# MAGI_sUART.net
KiCad netlist of a schematic drawn in Altium Designer
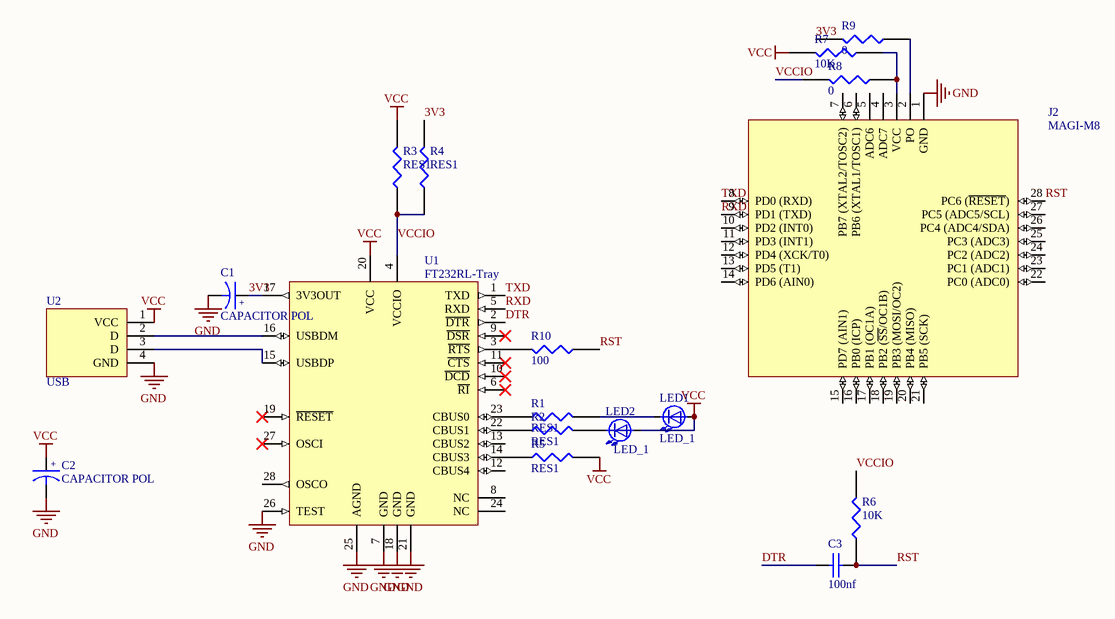
[diagram p0: MAGI'sUART.SchDoc]

(export (version "E")
  (design (tool "Eeschema 10.0.6"))
  (components
    (comp (ref "C1")
      (value "CAPACITOR POL")
      (footprint "6-0805_N")
      (description "Capacitor")
      (libsource (lib "电容器") (part "CAPACITOR POL"))
    )
    (comp (ref "C2")
      (value "CAPACITOR POL")
      (footprint "6-0805_N")
      (description "Capacitor")
      (libsource (lib "电容器") (part "CAPACITOR POL"))
    )
    (comp (ref "C3")
      (value "100nf")
      (footprint "6-0805_n")
      (description "Capacitor")
      (libsource (lib "电容器") (part "CAP_1"))
    )
    (comp (ref "J2") (value "MAGI-M8") (footprint "MAGI-M8") (libsource (lib "MAGI-M8") (part "MAGI-M8")))
    (comp (ref "LED1") (value "LED_1") (footprint "6-0805_N") (libsource (lib "二极管") (part "LED_1")))
    (comp (ref "LED2") (value "LED_1") (footprint "6-0805_N") (libsource (lib "二极管") (part "LED_1")))
    (comp (ref "R1") (value "RES1") (footprint "6-0805_n") (libsource (lib "电阻器") (part "RES1")))
    (comp (ref "R2") (value "RES1") (footprint "6-0805_n") (libsource (lib "电阻器") (part "RES1")))
    (comp (ref "R3") (value "RES1") (footprint "6-0805_N") (libsource (lib "电阻器") (part "RES1")))
    (comp (ref "R4") (value "RES1") (footprint "6-0805_N") (libsource (lib "电阻器") (part "RES1")))
    (comp (ref "R5") (value "RES1") (footprint "6-0805_N") (libsource (lib "电阻器") (part "RES1")))
    (comp (ref "R6") (value "10K") (footprint "6-0805_N") (libsource (lib "电阻器") (part "RES1")))
    (comp (ref "R7") (value "10K") (footprint "6-0805_N") (libsource (lib "电阻器") (part "RES1")))
    (comp (ref "R8") (value "0") (footprint "6-0805_N") (libsource (lib "电阻器") (part "RES1")))
    (comp (ref "R9") (value "0") (footprint "6-0805_N") (libsource (lib "电阻器") (part "RES1")))
    (comp (ref "R10") (value "100") (footprint "6-0805_N") (libsource (lib "电阻器") (part "RES1")))
    (comp (ref "U1")
      (value "FT232RL-Tray")
      (footprint "SSOP-28_N")
      (description "USB UART Asynchronous Serial Data Transfer Chip, SSOP-28, Tray")
      (fields (field (name "PUBLISHER") "Altium Limited"))
      (libsource (lib "FTDI Communication UART") (part "FT232RL-Tray"))
    )
    (comp (ref "U2") (value "USB") (footprint "MicroUSB") (libsource (lib "USB接口") (part "USB")))
  )
  (nets
    (net (code "1") (name "/3V3") (class "Default")
      (node (ref "C1") (pin "1") (pinfunction "1_1") (pintype "passive"))
      (node (ref "R4") (pin "2") (pinfunction "2_2") (pintype "passive"))
      (node (ref "R9") (pin "2") (pinfunction "2_2") (pintype "passive"))
      (node (ref "U1") (pin "17") (pinfunction "3V3OUT_17") (pintype "output"))
    )
    (net (code "2") (name "/DTR") (class "Default")
      (node (ref "C3") (pin "1") (pinfunction "1_1") (pintype "passive"))
      (node (ref "U1") (pin "2") (pinfunction "~{DTR}_2") (pintype "output"))
    )
    (net (code "3") (name "/RST") (class "Default")
      (node (ref "C3") (pin "2") (pinfunction "2_2") (pintype "passive"))
      (node (ref "J2") (pin "28") (pinfunction "PC6_(~{RESET})_28") (pintype "bidirectional"))
      (node (ref "R10") (pin "1") (pinfunction "1_1") (pintype "passive"))
      (node (ref "R6") (pin "1") (pinfunction "1_1") (pintype "passive"))
    )
    (net (code "4") (name "/RXD") (class "Default")
      (node (ref "J2") (pin "9") (pinfunction "PD1_(TXD)_9") (pintype "bidirectional"))
      (node (ref "U1") (pin "5") (pinfunction "RXD_5") (pintype "input"))
    )
    (net (code "5") (name "/TXD") (class "Default")
      (node (ref "J2") (pin "8") (pinfunction "PD0_(RXD)_8") (pintype "bidirectional"))
      (node (ref "U1") (pin "1") (pinfunction "TXD_1") (pintype "output"))
    )
    (net (code "6") (name "/VCCIO") (class "Default")
      (node (ref "R3") (pin "1") (pinfunction "1_1") (pintype "passive"))
      (node (ref "R4") (pin "1") (pinfunction "1_1") (pintype "passive"))
      (node (ref "R6") (pin "2") (pinfunction "2_2") (pintype "passive"))
      (node (ref "R8") (pin "2") (pinfunction "2_2") (pintype "passive"))
      (node (ref "U1") (pin "4") (pinfunction "VCCIO_4") (pintype "power_in"))
    )
    (net (code "7") (name "GND") (class "Default")
      (node (ref "C1") (pin "2") (pinfunction "2_2") (pintype "passive"))
      (node (ref "C2") (pin "2") (pinfunction "2_2") (pintype "passive"))
      (node (ref "J2") (pin "1") (pinfunction "GND_1") (pintype "power_in"))
      (node (ref "U1") (pin "18") (pinfunction "GND_18") (pintype "power_in"))
      (node (ref "U1") (pin "21") (pinfunction "GND_21") (pintype "power_in"))
      (node (ref "U1") (pin "25") (pinfunction "AGND_25") (pintype "power_in"))
      (node (ref "U1") (pin "26") (pinfunction "TEST_26") (pintype "input"))
      (node (ref "U1") (pin "7") (pinfunction "GND_7") (pintype "power_in"))
      (node (ref "U2") (pin "4") (pinfunction "GND_4") (pintype "passive"))
    )
    (net (code "8") (name "Net-(J2-PO)") (class "Default")
      (node (ref "J2") (pin "2") (pinfunction "PO_2") (pintype "power_in"))
      (node (ref "R9") (pin "1") (pinfunction "1_1") (pintype "passive"))
    )
    (net (code "9") (name "Net-(J2-VCC)") (class "Default")
      (node (ref "J2") (pin "3") (pinfunction "VCC_3") (pintype "power_in"))
      (node (ref "R7") (pin "1") (pinfunction "1_1") (pintype "passive"))
      (node (ref "R8") (pin "1") (pinfunction "1_1") (pintype "passive"))
    )
    (net (code "10") (name "Net-(LED1-K)") (class "Default")
      (node (ref "LED1") (pin "2") (pinfunction "K_2") (pintype "passive"))
      (node (ref "R1") (pin "2") (pinfunction "2_2") (pintype "passive"))
    )
    (net (code "11") (name "Net-(LED2-K)") (class "Default")
      (node (ref "LED2") (pin "2") (pinfunction "K_2") (pintype "passive"))
      (node (ref "R2") (pin "2") (pinfunction "2_2") (pintype "passive"))
    )
    (net (code "12") (name "Net-(U1-CBUS0)") (class "Default")
      (node (ref "R1") (pin "1") (pinfunction "1_1") (pintype "passive"))
      (node (ref "U1") (pin "23") (pinfunction "CBUS0_23") (pintype "bidirectional"))
    )
    (net (code "13") (name "Net-(U1-CBUS1)") (class "Default")
      (node (ref "R2") (pin "1") (pinfunction "1_1") (pintype "passive"))
      (node (ref "U1") (pin "22") (pinfunction "CBUS1_22") (pintype "bidirectional"))
    )
    (net (code "14") (name "Net-(U1-CBUS3)") (class "Default")
      (node (ref "R5") (pin "1") (pinfunction "1_1") (pintype "passive"))
      (node (ref "U1") (pin "14") (pinfunction "CBUS3_14") (pintype "bidirectional"))
    )
    (net (code "15") (name "Net-(U1-USBDM)") (class "Default")
      (node (ref "U1") (pin "16") (pinfunction "USBDM_16") (pintype "bidirectional"))
      (node (ref "U2") (pin "2") (pinfunction "D_2") (pintype "passive"))
    )
    (net (code "16") (name "Net-(U1-USBDP)") (class "Default")
      (node (ref "U1") (pin "15") (pinfunction "USBDP_15") (pintype "bidirectional"))
      (node (ref "U2") (pin "3") (pinfunction "D_3") (pintype "passive"))
    )
    (net (code "17") (name "Net-(U1-~{RTS})") (class "Default")
      (node (ref "R10") (pin "2") (pinfunction "2_2") (pintype "passive"))
      (node (ref "U1") (pin "3") (pinfunction "~{RTS}_3") (pintype "output"))
    )
    (net (code "18") (name "VCC") (class "Default")
      (node (ref "C2") (pin "1") (pinfunction "1_1") (pintype "passive"))
      (node (ref "LED1") (pin "1") (pinfunction "A_1") (pintype "passive"))
      (node (ref "LED2") (pin "1") (pinfunction "A_1") (pintype "passive"))
      (node (ref "R3") (pin "2") (pinfunction "2_2") (pintype "passive"))
      (node (ref "R5") (pin "2") (pinfunction "2_2") (pintype "passive"))
      (node (ref "R7") (pin "2") (pinfunction "2_2") (pintype "passive"))
      (node (ref "U1") (pin "20") (pinfunction "VCC_20") (pintype "power_in"))
      (node (ref "U2") (pin "1") (pinfunction "VCC_1") (pintype "passive"))
    )
    (net (code "19") (name "unconnected-(J2-ADC6-Pad5)") (class "Default")
      (node (ref "J2") (pin "5") (pinfunction "ADC6_5") (pintype "passive"))
    )
    (net (code "20") (name "unconnected-(J2-ADC7-Pad4)") (class "Default")
      (node (ref "J2") (pin "4") (pinfunction "ADC7_4") (pintype "passive"))
    )
    (net (code "21") (name "unconnected-(J2-PB0_(ICP)-Pad16)") (class "Default")
      (node (ref "J2") (pin "16") (pinfunction "PB0_(ICP)_16") (pintype "bidirectional"))
    )
    (net (code "22") (name "unconnected-(J2-PB1_(OC1A)-Pad17)") (class "Default")
      (node (ref "J2") (pin "17") (pinfunction "PB1_(OC1A)_17") (pintype "bidirectional"))
    )
    (net (code "23") (name "unconnected-(J2-PB2_(~{SS}{slash}OC1B)-Pad18)") (class "Default")
      (node (ref "J2") (pin "18") (pinfunction "PB2_(~{SS}/OC1B)_18") (pintype "bidirectional"))
    )
    (net (code "24") (name "unconnected-(J2-PB3_(MOSI{slash}OC2)-Pad19)") (class "Default")
      (node (ref "J2") (pin "19") (pinfunction "PB3_(MOSI/OC2)_19") (pintype "bidirectional"))
    )
    (net (code "25") (name "unconnected-(J2-PB4_(MISO)-Pad20)") (class "Default")
      (node (ref "J2") (pin "20") (pinfunction "PB4_(MISO)_20") (pintype "bidirectional"))
    )
    (net (code "26") (name "unconnected-(J2-PB5_(SCK)-Pad21)") (class "Default")
      (node (ref "J2") (pin "21") (pinfunction "PB5_(SCK)_21") (pintype "bidirectional"))
    )
    (net (code "27") (name "unconnected-(J2-PB6_(XTAL1{slash}TOSC1)-Pad6)") (class "Default")
      (node (ref "J2") (pin "6") (pinfunction "PB6_(XTAL1/TOSC1)_6") (pintype "bidirectional"))
    )
    (net (code "28") (name "unconnected-(J2-PB7_(XTAL2{slash}TOSC2)-Pad7)") (class "Default")
      (node (ref "J2") (pin "7") (pinfunction "PB7_(XTAL2/TOSC2)_7") (pintype "bidirectional"))
    )
    (net (code "29") (name "unconnected-(J2-PC0_(ADC0)-Pad22)") (class "Default")
      (node (ref "J2") (pin "22") (pinfunction "PC0_(ADC0)_22") (pintype "bidirectional"))
    )
    (net (code "30") (name "unconnected-(J2-PC1_(ADC1)-Pad23)") (class "Default")
      (node (ref "J2") (pin "23") (pinfunction "PC1_(ADC1)_23") (pintype "bidirectional"))
    )
    (net (code "31") (name "unconnected-(J2-PC2_(ADC2)-Pad24)") (class "Default")
      (node (ref "J2") (pin "24") (pinfunction "PC2_(ADC2)_24") (pintype "bidirectional"))
    )
    (net (code "32") (name "unconnected-(J2-PC3_(ADC3)-Pad25)") (class "Default")
      (node (ref "J2") (pin "25") (pinfunction "PC3_(ADC3)_25") (pintype "bidirectional"))
    )
    (net (code "33") (name "unconnected-(J2-PC4_(ADC4{slash}SDA)-Pad26)") (class "Default")
      (node (ref "J2") (pin "26") (pinfunction "PC4_(ADC4/SDA)_26") (pintype "bidirectional"))
    )
    (net (code "34") (name "unconnected-(J2-PC5_(ADC5{slash}SCL)-Pad27)") (class "Default")
      (node (ref "J2") (pin "27") (pinfunction "PC5_(ADC5/SCL)_27") (pintype "bidirectional"))
    )
    (net (code "35") (name "unconnected-(J2-PD2_(INT0)-Pad10)") (class "Default")
      (node (ref "J2") (pin "10") (pinfunction "PD2_(INT0)_10") (pintype "bidirectional"))
    )
    (net (code "36") (name "unconnected-(J2-PD3_(INT1)-Pad11)") (class "Default")
      (node (ref "J2") (pin "11") (pinfunction "PD3_(INT1)_11") (pintype "bidirectional"))
    )
    (net (code "37") (name "unconnected-(J2-PD4_(XCK{slash}T0)-Pad12)") (class "Default")
      (node (ref "J2") (pin "12") (pinfunction "PD4_(XCK/T0)_12") (pintype "bidirectional"))
    )
    (net (code "38") (name "unconnected-(J2-PD5_(T1)-Pad13)") (class "Default")
      (node (ref "J2") (pin "13") (pinfunction "PD5_(T1)_13") (pintype "bidirectional"))
    )
    (net (code "39") (name "unconnected-(J2-PD6_(AIN0)-Pad14)") (class "Default")
      (node (ref "J2") (pin "14") (pinfunction "PD6_(AIN0)_14") (pintype "bidirectional"))
    )
    (net (code "40") (name "unconnected-(J2-PD7_(AIN1)-Pad15)") (class "Default")
      (node (ref "J2") (pin "15") (pinfunction "PD7_(AIN1)_15") (pintype "bidirectional"))
    )
    (net (code "41") (name "unconnected-(U1-CBUS2-Pad13)") (class "Default")
      (node (ref "U1") (pin "13") (pinfunction "CBUS2_13") (pintype "bidirectional"))
    )
    (net (code "42") (name "unconnected-(U1-CBUS4-Pad12)") (class "Default")
      (node (ref "U1") (pin "12") (pinfunction "CBUS4_12") (pintype "bidirectional"))
    )
    (net (code "43") (name "unconnected-(U1-NC-Pad8)") (class "Default")
      (node (ref "U1") (pin "8") (pinfunction "NC_8") (pintype "passive"))
    )
    (net (code "44") (name "unconnected-(U1-NC-Pad24)") (class "Default")
      (node (ref "U1") (pin "24") (pinfunction "NC_24") (pintype "passive"))
    )
    (net (code "45") (name "unconnected-(U1-OSCI-Pad27)") (class "Default")
      (node (ref "U1") (pin "27") (pinfunction "OSCI_27") (pintype "input+no_connect"))
    )
    (net (code "46") (name "unconnected-(U1-OSCO-Pad28)") (class "Default")
      (node (ref "U1") (pin "28") (pinfunction "OSCO_28") (pintype "output"))
    )
    (net (code "47") (name "unconnected-(U1-~{CTS}-Pad11)") (class "Default")
      (node (ref "U1") (pin "11") (pinfunction "~{CTS}_11") (pintype "input+no_connect"))
    )
    (net (code "48") (name "unconnected-(U1-~{DCD}-Pad10)") (class "Default")
      (node (ref "U1") (pin "10") (pinfunction "~{DCD}_10") (pintype "input+no_connect"))
    )
    (net (code "49") (name "unconnected-(U1-~{DSR}-Pad9)") (class "Default")
      (node (ref "U1") (pin "9") (pinfunction "~{DSR}_9") (pintype "input+no_connect"))
    )
    (net (code "50") (name "unconnected-(U1-~{RESET}-Pad19)") (class "Default")
      (node (ref "U1") (pin "19") (pinfunction "~{RESET}_19") (pintype "input+no_connect"))
    )
    (net (code "51") (name "unconnected-(U1-~{RI}-Pad6)") (class "Default")
      (node (ref "U1") (pin "6") (pinfunction "~{RI}_6") (pintype "input+no_connect"))
    )
  )
)
